# Ariel_v5_5.net
KiCad netlist of a schematic drawn in EAGLE
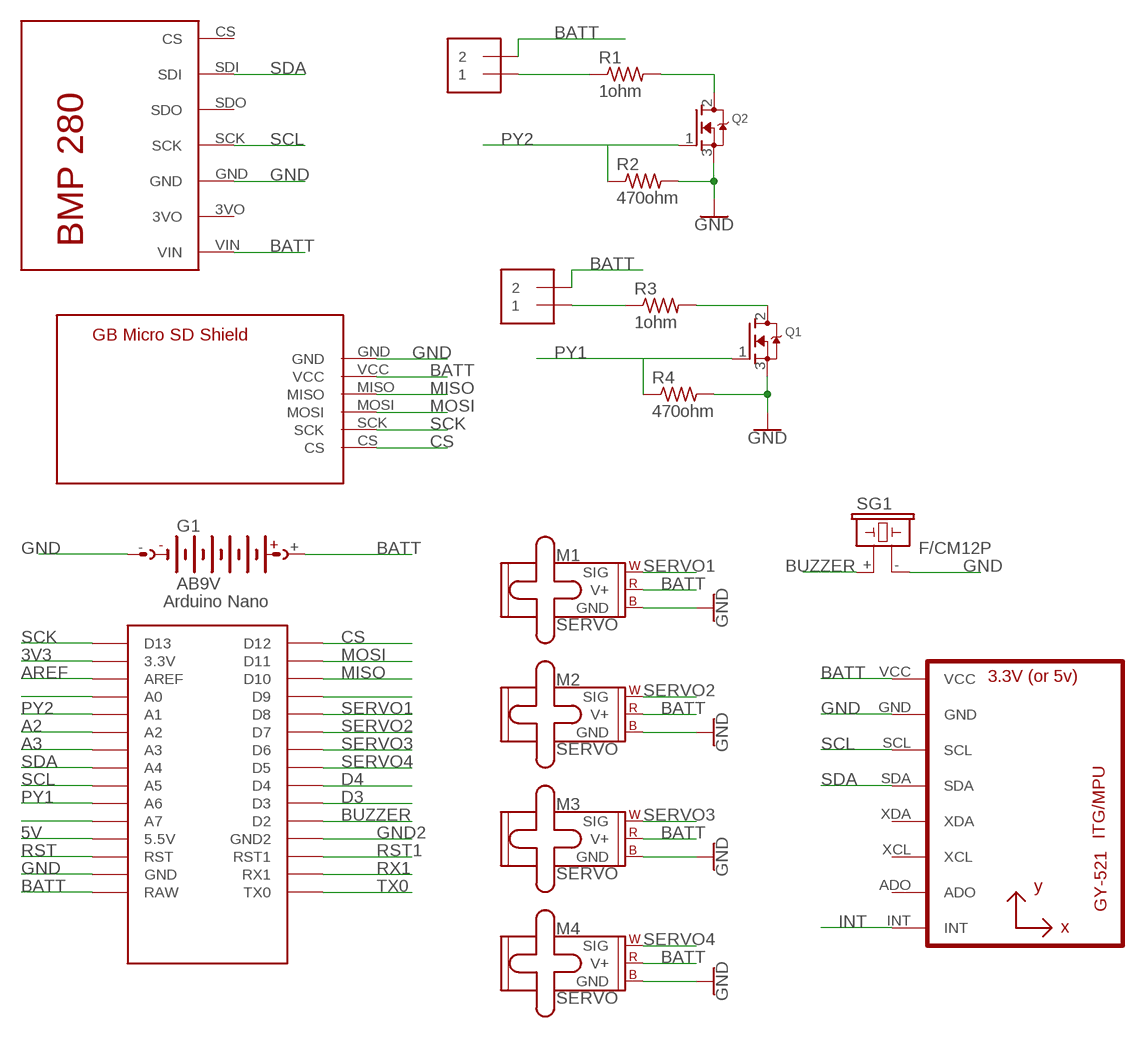
[diagram p0: schematic, sheet 1]

(export (version "E")
  (design (tool "Eeschema 10.0.6"))
  (components
    (comp (ref "G1")
      (value "AB9V")
      (footprint "eagle-import:AB9V")
      (libsource (lib "eagle-import") (part "AB9V"))
    )
    (comp (ref "J1")
      (value "1X2-3.5MM")
      (footprint "eagle-import:1X2-3.5MM")
      (libsource (lib "eagle-import") (part "1X2-3.5MM"))
    )
    (comp (ref "J2")
      (value "1X2-3.5MM")
      (footprint "eagle-import:1X2-3.5MM")
      (libsource (lib "eagle-import") (part "1X2-3.5MM"))
    )
    (comp (ref "M1")
      (value "SERVO")
      (footprint "eagle-import:1X03")
      (libsource (lib "eagle-import") (part "SERVO"))
    )
    (comp (ref "M2")
      (value "SERVO")
      (footprint "eagle-import:1X03")
      (libsource (lib "eagle-import") (part "SERVO"))
    )
    (comp (ref "M3")
      (value "SERVO")
      (footprint "eagle-import:1X03")
      (libsource (lib "eagle-import") (part "SERVO"))
    )
    (comp (ref "M4")
      (value "SERVO")
      (footprint "eagle-import:1X03")
      (libsource (lib "eagle-import") (part "SERVO"))
    )
    (comp (ref "Q1")
      (value "MOSFET-NGDS_TO220V")
      (footprint "eagle-import:TO220V")
      (libsource (lib "eagle-import") (part "MOSFET-NGDS_TO220V"))
    )
    (comp (ref "Q2")
      (value "MOSFET-NGDS_TO220V")
      (footprint "eagle-import:TO220V")
      (libsource (lib "eagle-import") (part "MOSFET-NGDS_TO220V"))
    )
    (comp (ref "R1")
      (value "1ohm")
      (footprint "eagle-import:0805-THM")
      (libsource (lib "eagle-import") (part "FLIPFLOP-RES"))
    )
    (comp (ref "R2")
      (value "470ohm")
      (footprint "eagle-import:0805-THM")
      (libsource (lib "eagle-import") (part "FLIPFLOP-RES"))
    )
    (comp (ref "R3")
      (value "1ohm")
      (footprint "eagle-import:0805-THM")
      (libsource (lib "eagle-import") (part "FLIPFLOP-RES"))
    )
    (comp (ref "R4")
      (value "470ohm")
      (footprint "eagle-import:0805-THM")
      (libsource (lib "eagle-import") (part "FLIPFLOP-RES"))
    )
    (comp (ref "SG1")
      (value "F/CM12P")
      (footprint "eagle-import:F_CM12P")
      (libsource (lib "eagle-import") (part "F/CM12P"))
    )
    (comp (ref "U$1")
      (value "NANO")
      (footprint "eagle-import:NANO")
      (libsource (lib "eagle-import") (part "NANO"))
    )
    (comp (ref "U$2")
      (value "BMP280")
      (footprint "eagle-import:BMP280")
      (libsource (lib "eagle-import") (part "BMP280"))
    )
    (comp (ref "U$3")
      (value "GBMICROSDSHIELD")
      (footprint "eagle-import:GBMICROSDSHIELD")
      (libsource (lib "eagle-import") (part "GBMICROSDSHIELD"))
    )
    (comp (ref "U1")
      (value "GY-521MPU6050")
      (footprint "eagle-import:GY-521")
      (libsource (lib "eagle-import") (part "GY-521MPU6050"))
    )
  )
  (nets
    (net (code "1") (name "/3V3") (class "Default")
      (node (ref "U$1") (pin "3.3V") (pinfunction "3.3V_3.3V") (pintype "bidirectional"))
    )
    (net (code "2") (name "/5V") (class "Default")
      (node (ref "U$1") (pin "5V") (pinfunction "5.5V_5V") (pintype "bidirectional"))
    )
    (net (code "3") (name "/A2") (class "Default")
      (node (ref "U$1") (pin "A2") (pinfunction "A2_A2") (pintype "bidirectional"))
    )
    (net (code "4") (name "/A3") (class "Default")
      (node (ref "U$1") (pin "A3") (pinfunction "A3_A3") (pintype "bidirectional"))
    )
    (net (code "5") (name "/AREF") (class "Default")
      (node (ref "U$1") (pin "AREF") (pinfunction "AREF_AREF") (pintype "bidirectional"))
    )
    (net (code "6") (name "/BATT") (class "Default")
      (node (ref "G1") (pin "+") (pinfunction "+_+") (pintype "passive"))
      (node (ref "J1") (pin "2") (pinfunction "2_2") (pintype "passive"))
      (node (ref "J2") (pin "2") (pinfunction "2_2") (pintype "passive"))
      (node (ref "M1") (pin "2") (pinfunction "V+_2") (pintype "bidirectional"))
      (node (ref "M2") (pin "2") (pinfunction "V+_2") (pintype "bidirectional"))
      (node (ref "M3") (pin "2") (pinfunction "V+_2") (pintype "bidirectional"))
      (node (ref "M4") (pin "2") (pinfunction "V+_2") (pintype "bidirectional"))
      (node (ref "U$1") (pin "RAW") (pinfunction "RAW_RAW") (pintype "bidirectional"))
      (node (ref "U$2") (pin "VIN") (pinfunction "VIN_VIN") (pintype "bidirectional"))
      (node (ref "U$3") (pin "VCC") (pinfunction "VCC_VCC") (pintype "bidirectional"))
      (node (ref "U1") (pin "VCC") (pinfunction "VCC_VCC") (pintype "bidirectional"))
    )
    (net (code "7") (name "/BUZZER") (class "Default")
      (node (ref "SG1") (pin "+") (pinfunction "1_+") (pintype "passive"))
      (node (ref "U$1") (pin "D2") (pinfunction "D2_D2") (pintype "bidirectional"))
    )
    (net (code "8") (name "/CS") (class "Default")
      (node (ref "U$1") (pin "D12") (pinfunction "D12_D12") (pintype "bidirectional"))
      (node (ref "U$3") (pin "CS") (pinfunction "CS_CS") (pintype "bidirectional"))
    )
    (net (code "9") (name "/D3") (class "Default")
      (node (ref "U$1") (pin "D3") (pinfunction "D3_D3") (pintype "bidirectional"))
    )
    (net (code "10") (name "/D4") (class "Default")
      (node (ref "U$1") (pin "D4") (pinfunction "D4_D4") (pintype "bidirectional"))
    )
    (net (code "11") (name "/GND2") (class "Default")
      (node (ref "U$1") (pin "GND1") (pinfunction "GND2_GND1") (pintype "bidirectional"))
    )
    (net (code "12") (name "/INT") (class "Default")
      (node (ref "U1") (pin "INT") (pinfunction "INT_INT") (pintype "bidirectional"))
    )
    (net (code "13") (name "/MISO") (class "Default")
      (node (ref "U$1") (pin "D10") (pinfunction "D10_D10") (pintype "bidirectional"))
      (node (ref "U$3") (pin "MISO") (pinfunction "MISO_MISO") (pintype "bidirectional"))
    )
    (net (code "14") (name "/MOSI") (class "Default")
      (node (ref "U$1") (pin "D11") (pinfunction "D11_D11") (pintype "bidirectional"))
      (node (ref "U$3") (pin "MOSI") (pinfunction "MOSI_MOSI") (pintype "bidirectional"))
    )
    (net (code "15") (name "/PY1") (class "Default")
      (node (ref "Q1") (pin "1") (pinfunction "G_1") (pintype "bidirectional"))
      (node (ref "R4") (pin "1") (pinfunction "1_1") (pintype "passive"))
      (node (ref "U$1") (pin "A6") (pinfunction "A6_A6") (pintype "bidirectional"))
    )
    (net (code "16") (name "/PY2") (class "Default")
      (node (ref "Q2") (pin "1") (pinfunction "G_1") (pintype "bidirectional"))
      (node (ref "R2") (pin "1") (pinfunction "1_1") (pintype "passive"))
      (node (ref "U$1") (pin "A1") (pinfunction "A1_A1") (pintype "bidirectional"))
    )
    (net (code "17") (name "/RST") (class "Default")
      (node (ref "U$1") (pin "RST") (pinfunction "RST_RST") (pintype "bidirectional"))
    )
    (net (code "18") (name "/RST1") (class "Default")
      (node (ref "U$1") (pin "RST1") (pinfunction "RST1_RST1") (pintype "bidirectional"))
    )
    (net (code "19") (name "/RX1") (class "Default")
      (node (ref "U$1") (pin "RX1") (pinfunction "RX1_RX1") (pintype "bidirectional"))
    )
    (net (code "20") (name "/SCK") (class "Default")
      (node (ref "U$1") (pin "D13") (pinfunction "D13_D13") (pintype "bidirectional"))
      (node (ref "U$3") (pin "SCK") (pinfunction "SCK_SCK") (pintype "bidirectional"))
    )
    (net (code "21") (name "/SCL") (class "Default")
      (node (ref "U$1") (pin "A5") (pinfunction "A5_A5") (pintype "bidirectional"))
      (node (ref "U$2") (pin "SCK") (pinfunction "SCK_SCK") (pintype "bidirectional"))
      (node (ref "U1") (pin "SCL") (pinfunction "SCL_SCL") (pintype "bidirectional"))
    )
    (net (code "22") (name "/SDA") (class "Default")
      (node (ref "U$1") (pin "A4") (pinfunction "A4_A4") (pintype "bidirectional"))
      (node (ref "U$2") (pin "SDI") (pinfunction "SDI_SDI") (pintype "bidirectional"))
      (node (ref "U1") (pin "SDA") (pinfunction "SDA_SDA") (pintype "bidirectional"))
    )
    (net (code "23") (name "/SERVO1") (class "Default")
      (node (ref "M1") (pin "1") (pinfunction "SIG_1") (pintype "bidirectional"))
      (node (ref "U$1") (pin "D8") (pinfunction "D8_D8") (pintype "bidirectional"))
    )
    (net (code "24") (name "/SERVO2") (class "Default")
      (node (ref "M2") (pin "1") (pinfunction "SIG_1") (pintype "bidirectional"))
      (node (ref "U$1") (pin "D7") (pinfunction "D7_D7") (pintype "bidirectional"))
    )
    (net (code "25") (name "/SERVO3") (class "Default")
      (node (ref "M3") (pin "1") (pinfunction "SIG_1") (pintype "bidirectional"))
      (node (ref "U$1") (pin "D6") (pinfunction "D6_D6") (pintype "bidirectional"))
    )
    (net (code "26") (name "/SERVO4") (class "Default")
      (node (ref "M4") (pin "1") (pinfunction "SIG_1") (pintype "bidirectional"))
      (node (ref "U$1") (pin "D5") (pinfunction "D5_D5") (pintype "bidirectional"))
    )
    (net (code "27") (name "/TX0") (class "Default")
      (node (ref "U$1") (pin "TX0") (pinfunction "TX0_TX0") (pintype "bidirectional"))
    )
    (net (code "28") (name "GND") (class "Default")
      (node (ref "G1") (pin "-") (pinfunction "-_-") (pintype "passive"))
      (node (ref "M1") (pin "3") (pinfunction "GND_3") (pintype "bidirectional"))
      (node (ref "M2") (pin "3") (pinfunction "GND_3") (pintype "bidirectional"))
      (node (ref "M3") (pin "3") (pinfunction "GND_3") (pintype "bidirectional"))
      (node (ref "M4") (pin "3") (pinfunction "GND_3") (pintype "bidirectional"))
      (node (ref "Q1") (pin "3") (pinfunction "S_3") (pintype "bidirectional"))
      (node (ref "Q2") (pin "3") (pinfunction "S_3") (pintype "bidirectional"))
      (node (ref "R2") (pin "2") (pinfunction "2_2") (pintype "passive"))
      (node (ref "R4") (pin "2") (pinfunction "2_2") (pintype "passive"))
      (node (ref "SG1") (pin "-") (pinfunction "2_-") (pintype "passive"))
      (node (ref "U$1") (pin "GND") (pinfunction "GND_GND") (pintype "bidirectional"))
      (node (ref "U$2") (pin "GND") (pinfunction "GND_GND") (pintype "bidirectional"))
      (node (ref "U$3") (pin "GND") (pinfunction "GND_GND") (pintype "bidirectional"))
      (node (ref "U1") (pin "GND") (pinfunction "GND_GND") (pintype "bidirectional"))
    )
    (net (code "29") (name "Net-(J1-Pad1)") (class "Default")
      (node (ref "J1") (pin "1") (pinfunction "1_1") (pintype "passive"))
      (node (ref "R1") (pin "1") (pinfunction "1_1") (pintype "passive"))
    )
    (net (code "30") (name "Net-(J2-Pad1)") (class "Default")
      (node (ref "J2") (pin "1") (pinfunction "1_1") (pintype "passive"))
      (node (ref "R3") (pin "1") (pinfunction "1_1") (pintype "passive"))
    )
    (net (code "31") (name "Net-(Q1-D)") (class "Default")
      (node (ref "Q1") (pin "2") (pinfunction "D_2") (pintype "bidirectional"))
      (node (ref "R3") (pin "2") (pinfunction "2_2") (pintype "passive"))
    )
    (net (code "32") (name "Net-(Q2-D)") (class "Default")
      (node (ref "Q2") (pin "2") (pinfunction "D_2") (pintype "bidirectional"))
      (node (ref "R1") (pin "2") (pinfunction "2_2") (pintype "passive"))
    )
    (net (code "33") (name "unconnected-(U$1-PadA0)") (class "Default")
      (node (ref "U$1") (pin "A0") (pinfunction "A0_A0") (pintype "bidirectional"))
    )
    (net (code "34") (name "unconnected-(U$1-PadA7)") (class "Default")
      (node (ref "U$1") (pin "A7") (pinfunction "A7_A7") (pintype "bidirectional"))
    )
    (net (code "35") (name "unconnected-(U$1-PadD9)") (class "Default")
      (node (ref "U$1") (pin "D9") (pinfunction "D9_D9") (pintype "bidirectional"))
    )
    (net (code "36") (name "unconnected-(U$1-PadICSP1)") (class "Default")
      (node (ref "U$1") (pin "ICSP1") (pinfunction "ICSP1_ICSP1") (pintype "bidirectional"))
    )
    (net (code "37") (name "unconnected-(U$1-PadICSP2)") (class "Default")
      (node (ref "U$1") (pin "ICSP2") (pinfunction "ICSP2_ICSP2") (pintype "bidirectional"))
    )
    (net (code "38") (name "unconnected-(U$1-PadICSP3)") (class "Default")
      (node (ref "U$1") (pin "ICSP3") (pinfunction "ICSP3_ICSP3") (pintype "bidirectional"))
    )
    (net (code "39") (name "unconnected-(U$1-PadICSP4)") (class "Default")
      (node (ref "U$1") (pin "ICSP4") (pinfunction "ICSP4_ICSP4") (pintype "bidirectional"))
    )
    (net (code "40") (name "unconnected-(U$1-PadICSP5)") (class "Default")
      (node (ref "U$1") (pin "ICSP5") (pinfunction "ICSP5_ICSP5") (pintype "bidirectional"))
    )
    (net (code "41") (name "unconnected-(U$1-PadICSP6)") (class "Default")
      (node (ref "U$1") (pin "ICSP6") (pinfunction "ICSP6_ICSP6") (pintype "bidirectional"))
    )
    (net (code "42") (name "unconnected-(U$2-Pad3VO)") (class "Default")
      (node (ref "U$2") (pin "3VO") (pinfunction "3VO_3VO") (pintype "bidirectional"))
    )
    (net (code "43") (name "unconnected-(U$2-PadCS)") (class "Default")
      (node (ref "U$2") (pin "CS") (pinfunction "CS_CS") (pintype "bidirectional"))
    )
    (net (code "44") (name "unconnected-(U$2-PadSDO)") (class "Default")
      (node (ref "U$2") (pin "SDO") (pinfunction "SDO_SDO") (pintype "bidirectional"))
    )
    (net (code "45") (name "unconnected-(U1-PadADO)") (class "Default")
      (node (ref "U1") (pin "ADO") (pinfunction "ADO_ADO") (pintype "bidirectional"))
    )
    (net (code "46") (name "unconnected-(U1-PadXCL)") (class "Default")
      (node (ref "U1") (pin "XCL") (pinfunction "XCL_XCL") (pintype "bidirectional"))
    )
    (net (code "47") (name "unconnected-(U1-PadXDA)") (class "Default")
      (node (ref "U1") (pin "XDA") (pinfunction "XDA_XDA") (pintype "bidirectional"))
    )
  )
)
